# asomator1.net
KiCad netlist of a schematic drawn in EAGLE
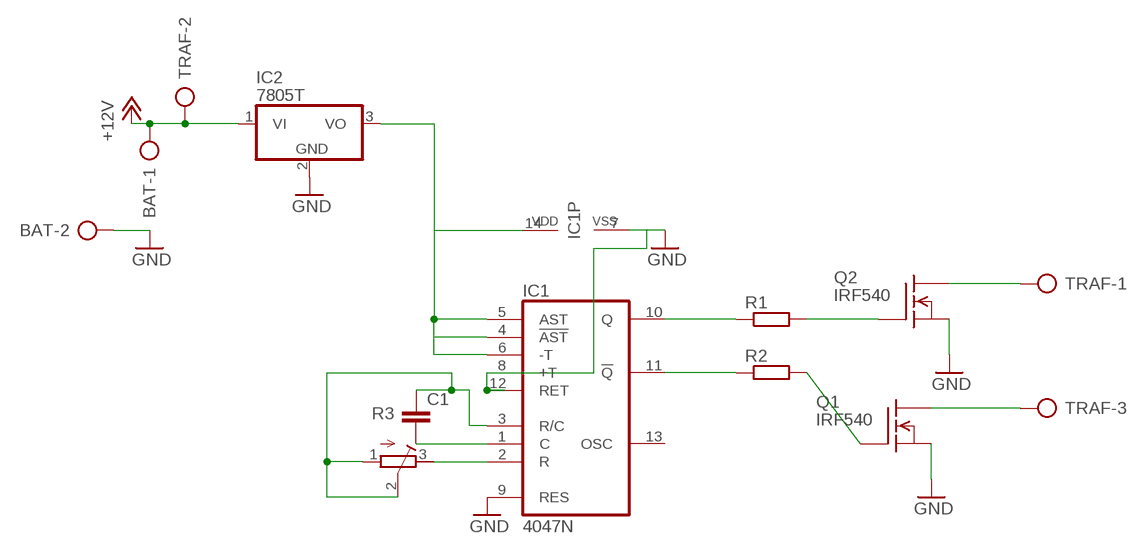
[diagram p0: schematic, sheet 1]

(export (version "E")
  (design (tool "Eeschema 10.0.6"))
  (components
    (comp (ref "BAT")
      (value "AK500/2-H")
      (footprint "eagle-import:AK500_2-H")
      (libsource (lib "eagle-import") (part "AK500/2-H"))
    )
    (comp (ref "C1")
      (value "C-EU025-030X050")
      (footprint "eagle-import:C025-030X050")
      (libsource (lib "eagle-import") (part "C-EU025-030X050"))
    )
    (comp (ref "IC1")
      (value "4047N")
      (footprint "eagle-import:DIL14")
      (libsource (lib "eagle-import") (part "4047N"))
    )
    (comp (ref "IC2")
      (value "7805T")
      (footprint "eagle-import:TO220H")
      (libsource (lib "eagle-import") (part "78T05"))
    )
    (comp (ref "Q1")
      (value "IRF540")
      (footprint "eagle-import:TO220")
      (libsource (lib "eagle-import") (part "IRF540"))
    )
    (comp (ref "Q2")
      (value "IRF540")
      (footprint "eagle-import:TO220")
      (libsource (lib "eagle-import") (part "IRF540"))
    )
    (comp (ref "R1")
      (value "R-EU_0204/7")
      (footprint "eagle-import:0204_7")
      (libsource (lib "eagle-import") (part "R-EU_0204/7"))
    )
    (comp (ref "R2")
      (value "R-EU_0204/7")
      (footprint "eagle-import:0204_7")
      (libsource (lib "eagle-import") (part "R-EU_0204/7"))
    )
    (comp (ref "R3")
      (value "R-TRIMM64P")
      (footprint "eagle-import:RTRIM64P")
      (libsource (lib "eagle-import") (part "R-TRIMM64P"))
    )
    (comp (ref "TRAF")
      (value "AK500/3-H")
      (footprint "eagle-import:AK500_3-H")
      (libsource (lib "eagle-import") (part "AK500/3-H"))
    )
  )
  (nets
    (net (code "1") (name "+12V") (class "Default")
      (node (ref "BAT") (pin "1") (pinfunction "KL_1") (pintype "passive"))
      (node (ref "IC2") (pin "1") (pinfunction "VI_1") (pintype "input"))
      (node (ref "TRAF") (pin "2") (pinfunction "KL_2") (pintype "passive"))
    )
    (net (code "2") (name "GND") (class "Default")
      (node (ref "BAT") (pin "2") (pinfunction "KL_2") (pintype "passive"))
      (node (ref "IC1") (pin "12") (pinfunction "RET_12") (pintype "input"))
      (node (ref "IC1") (pin "7") (pinfunction "VSS_7") (pintype "power_in"))
      (node (ref "IC1") (pin "8") (pinfunction "+T_8") (pintype "input"))
      (node (ref "IC1") (pin "9") (pinfunction "RES_9") (pintype "input"))
      (node (ref "IC2") (pin "2") (pinfunction "GND_2") (pintype "passive"))
      (node (ref "Q1") (pin "3") (pinfunction "S_3") (pintype "passive"))
      (node (ref "Q2") (pin "3") (pinfunction "S_3") (pintype "passive"))
    )
    (net (code "3") (name "Net-(IC1A--T)") (class "Default")
      (node (ref "IC1") (pin "14") (pinfunction "VDD_14") (pintype "power_in"))
      (node (ref "IC1") (pin "4") (pinfunction "~{AST}_4") (pintype "input"))
      (node (ref "IC1") (pin "5") (pinfunction "AST_5") (pintype "input"))
      (node (ref "IC1") (pin "6") (pinfunction "-T_6") (pintype "input"))
      (node (ref "IC2") (pin "3") (pinfunction "VO_3") (pintype "passive"))
    )
    (net (code "4") (name "Net-(IC1A-C)") (class "Default")
      (node (ref "C1") (pin "2") (pinfunction "2_2") (pintype "passive"))
      (node (ref "IC1") (pin "1") (pinfunction "C_1") (pintype "input"))
    )
    (net (code "5") (name "Net-(IC1A-Q)") (class "Default")
      (node (ref "IC1") (pin "10") (pinfunction "Q_10") (pintype "output"))
      (node (ref "R1") (pin "1") (pinfunction "1_1") (pintype "passive"))
    )
    (net (code "6") (name "Net-(IC1A-R)") (class "Default")
      (node (ref "IC1") (pin "2") (pinfunction "R_2") (pintype "input"))
      (node (ref "R3") (pin "3") (pinfunction "E_3") (pintype "passive"))
    )
    (net (code "7") (name "Net-(IC1A-R{slash}C)") (class "Default")
      (node (ref "C1") (pin "1") (pinfunction "1_1") (pintype "passive"))
      (node (ref "IC1") (pin "3") (pinfunction "R/C_3") (pintype "input"))
      (node (ref "R3") (pin "1") (pinfunction "A_1") (pintype "passive"))
      (node (ref "R3") (pin "2") (pinfunction "S_2") (pintype "passive"))
    )
    (net (code "8") (name "Net-(IC1A-~{Q})") (class "Default")
      (node (ref "IC1") (pin "11") (pinfunction "~{Q}_11") (pintype "output"))
      (node (ref "R2") (pin "1") (pinfunction "1_1") (pintype "passive"))
    )
    (net (code "9") (name "Net-(Q1-D)") (class "Default")
      (node (ref "Q1") (pin "2") (pinfunction "D_2") (pintype "passive"))
      (node (ref "TRAF") (pin "3") (pinfunction "KL_3") (pintype "passive"))
    )
    (net (code "10") (name "Net-(Q1-G)") (class "Default")
      (node (ref "Q1") (pin "1") (pinfunction "G_1") (pintype "passive"))
      (node (ref "R2") (pin "2") (pinfunction "2_2") (pintype "passive"))
    )
    (net (code "11") (name "Net-(Q2-D)") (class "Default")
      (node (ref "Q2") (pin "2") (pinfunction "D_2") (pintype "passive"))
      (node (ref "TRAF") (pin "1") (pinfunction "KL_1") (pintype "passive"))
    )
    (net (code "12") (name "Net-(Q2-G)") (class "Default")
      (node (ref "Q2") (pin "1") (pinfunction "G_1") (pintype "passive"))
      (node (ref "R1") (pin "2") (pinfunction "2_2") (pintype "passive"))
    )
    (net (code "13") (name "unconnected-(IC1A-OSC-Pad13)") (class "Default")
      (node (ref "IC1") (pin "13") (pinfunction "OSC_13") (pintype "output"))
    )
  )
)
